# ALIM_MOSFET.net
KiCad netlist of a schematic drawn in Altium Designer
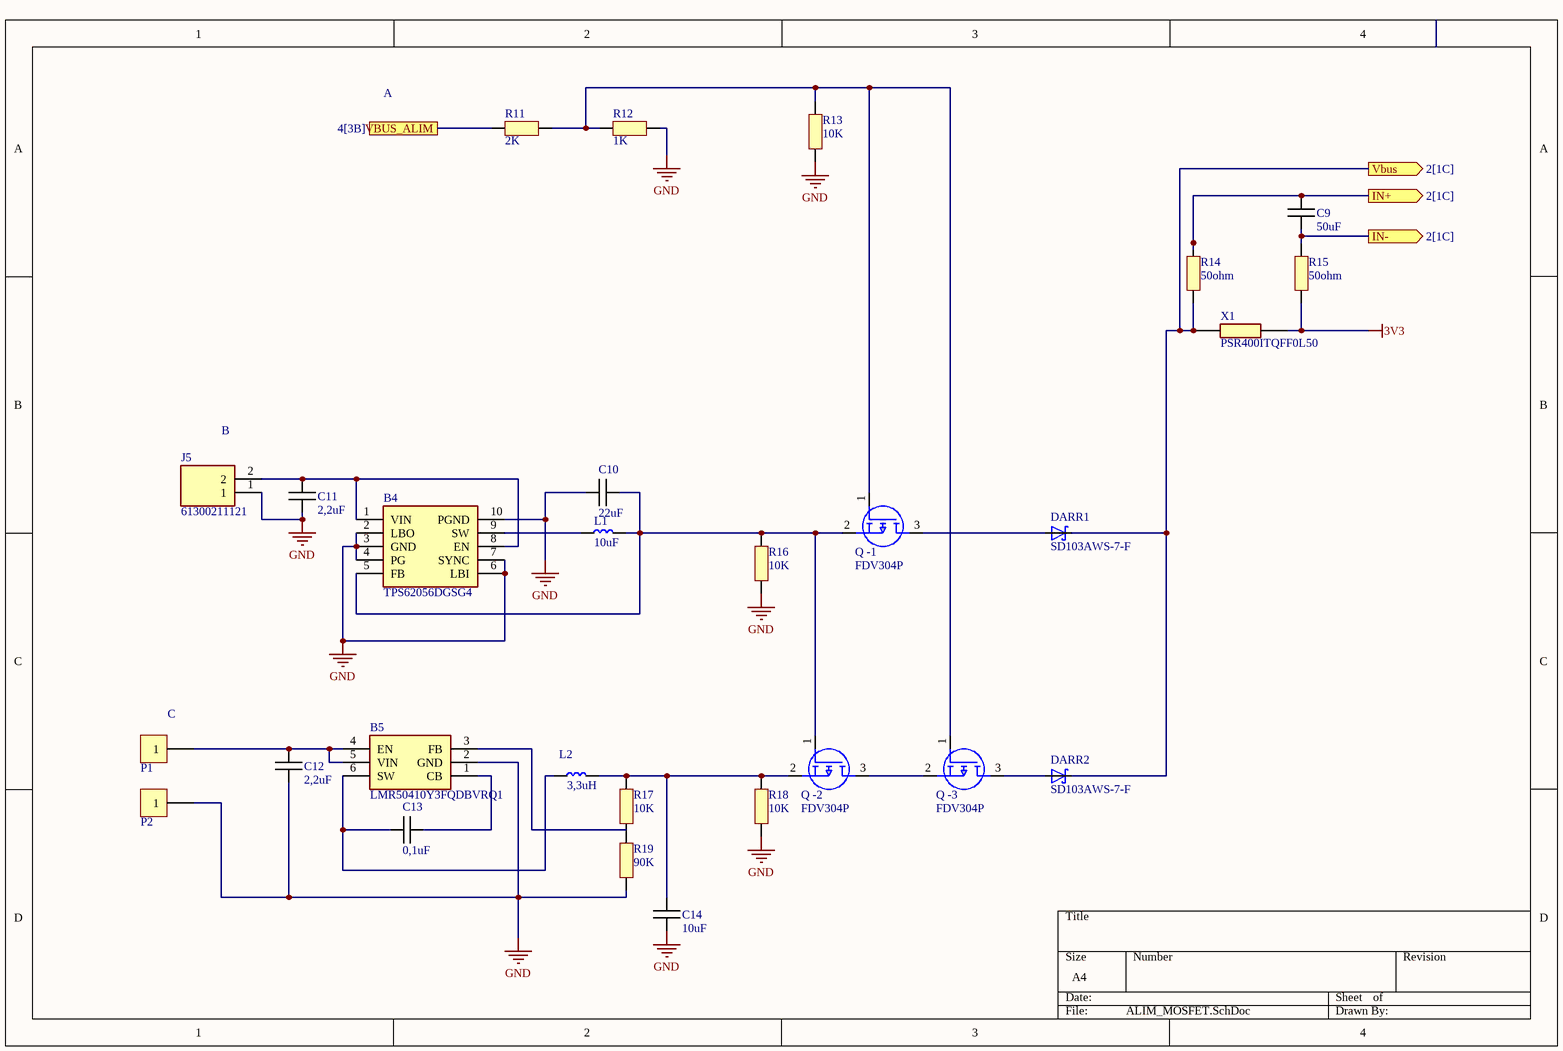
[diagram p0: ALIM_MOSFET.SchDoc]

(export (version "E")
  (design (tool "Eeschema 10.0.6"))
  (components
    (comp (ref "B4")
      (value "TPS62056DGSG4")
      (footprint "SOP50P490X110-10N")
      (fields (field (name "MOUSER PART NUMBER") "595-TPS62056DGSG4"))
      (libsource (lib "SCHLibrary") (part "TPS62056DGSG4"))
    )
    (comp (ref "B5")
      (value "LMR50410Y3FQDBVRQ1")
      (footprint "SOT95P280X145-6N")
      (fields (field (name "MOUSER PART NUMBER") "595-R50410Y3FQDBVRQ1"))
      (libsource (lib "SCHLibrary") (part "LMR50410Y3FQDBVRQ1"))
    )
    (comp (ref "C9")
      (value "50uF")
      (footprint "CAPC1005X06N")
      (libsource (lib "SCHLibrary") (part "Capacitor"))
    )
    (comp (ref "C10")
      (value "22uF")
      (footprint "CAPC1005X06N")
      (libsource (lib "SCHLibrary") (part "Capacitor"))
    )
    (comp (ref "C11")
      (value "2,2uF")
      (footprint "CAPC1005X06N")
      (libsource (lib "SCHLibrary") (part "Capacitor"))
    )
    (comp (ref "C12")
      (value "2,2uF")
      (footprint "CAPC1005X06N")
      (libsource (lib "SCHLibrary") (part "Capacitor"))
    )
    (comp (ref "C13")
      (value "0,1uF")
      (footprint "CAPC1005X06N")
      (libsource (lib "SCHLibrary") (part "Capacitor"))
    )
    (comp (ref "C14")
      (value "10uF")
      (footprint "CAPC1005X06N")
      (libsource (lib "SCHLibrary") (part "Capacitor"))
    )
    (comp (ref "DARR1")
      (value "SD103AWS-7-F")
      (footprint "SD103AWS-7-F")
      (description "Diode Array 3 Independent Schottky 40V 175mA Surface Mount 6-TSSOP, SC-88, SOT-363")
      (libsource (lib "SCHLibrary") (part "SD103AWS-7-F"))
    )
    (comp (ref "DARR2")
      (value "SD103AWS-7-F")
      (footprint "SD103AWS-7-F")
      (description "Diode Array 3 Independent Schottky 40V 175mA Surface Mount 6-TSSOP, SC-88, SOT-363")
      (libsource (lib "SCHLibrary") (part "SD103AWS-7-F"))
    )
    (comp (ref "J5")
      (value "61300211121")
      (footprint "61300211121")
      (description "WURTH ELEKTRONIK - 61300211121 - HEADER, 2.54MM, PIN, THT, VERTICAL, 2WAY")
      (libsource (lib "SCHLibrary") (part "61300211121"))
    )
    (comp (ref "L1") (value "10uF") (footprint "LQPC1005X06N") (libsource (lib "SCHLibrary") (part "Bobine")))
    (comp (ref "L2")
      (value "3,3uH")
      (footprint "LQPC1005X06N")
      (libsource (lib "SCHLibrary") (part "Bobine"))
    )
    (comp (ref "P1")
      (value "Plage CMS 10x5")
      (footprint "Plage CMS 10x5")
      (description "Plage de report CMS 10x5mm")
      (libsource (lib "SCHLibrary") (part "Plage CMS 10x5"))
    )
    (comp (ref "P2")
      (value "Plage CMS 10x5")
      (footprint "Plage CMS 10x5")
      (description "Plage de report CMS 10x5mm")
      (libsource (lib "SCHLibrary") (part "Plage CMS 10x5"))
    )
    (comp (ref "Q -1")
      (value "FDV304P")
      (footprint "SOT95P251X112-3N")
      (fields (field (name "MOUSER PART NUMBER") "512-FDV304P"))
      (libsource (lib "SCHLibrary") (part "FDV304P"))
    )
    (comp (ref "Q -2")
      (value "FDV304P")
      (footprint "SOT95P251X112-3N")
      (fields (field (name "MOUSER PART NUMBER") "512-FDV304P"))
      (libsource (lib "SCHLibrary") (part "FDV304P"))
    )
    (comp (ref "Q -3")
      (value "FDV304P")
      (footprint "SOT95P251X112-3N")
      (fields (field (name "MOUSER PART NUMBER") "512-FDV304P"))
      (libsource (lib "SCHLibrary") (part "FDV304P"))
    )
    (comp (ref "R11")
      (value "2K")
      (footprint "RESC1005X06N")
      (libsource (lib "SCHLibrary") (part "Resistor"))
    )
    (comp (ref "R12")
      (value "1K")
      (footprint "RESC1005X06N")
      (libsource (lib "SCHLibrary") (part "Resistor"))
    )
    (comp (ref "R13") (value "10K") (footprint "RESC1005X06N") (libsource (lib "") (part "Resistor_1")))
    (comp (ref "R14") (value "50ohm") (footprint "RESC1005X06N") (libsource (lib "") (part "Resistor_2")))
    (comp (ref "R15") (value "50ohm") (footprint "RESC1005X06N") (libsource (lib "") (part "Resistor_2")))
    (comp (ref "R16") (value "10K") (footprint "RESC1005X06N") (libsource (lib "") (part "Resistor_1")))
    (comp (ref "R17") (value "10K") (footprint "RESC1005X06N") (libsource (lib "") (part "Resistor_1")))
    (comp (ref "R18") (value "10K") (footprint "RESC1005X06N") (libsource (lib "") (part "Resistor_1")))
    (comp (ref "R19") (value "90K") (footprint "RESC1005X06N") (libsource (lib "") (part "Resistor_1")))
    (comp (ref "X1")
      (value "PSR400ITQFF0L50")
      (footprint "RESC10052X200N")
      (fields (field (name "MOUSER PART NUMBER") "755-PSR400ITQFF0L50"))
      (libsource (lib "SCHLibrary") (part "PSR400ITQFF0L50"))
    )
  )
  (nets
    (net (code "1") (name "/IN+") (class "Default")
      (node (ref "C9") (pin "1") (pinfunction "1_1") (pintype "passive"))
      (node (ref "R14") (pin "2") (pinfunction "2_2") (pintype "passive"))
    )
    (net (code "2") (name "/IN-") (class "Default")
      (node (ref "C9") (pin "2") (pinfunction "2_2") (pintype "passive"))
      (node (ref "R15") (pin "2") (pinfunction "2_2") (pintype "passive"))
    )
    (net (code "3") (name "/VBUS_ALIM") (class "Default")
      (node (ref "R11") (pin "1") (pinfunction "1_1") (pintype "passive"))
    )
    (net (code "4") (name "/Vbus") (class "Default")
      (node (ref "DARR1") (pin "1") (pinfunction "C_1") (pintype "passive"))
      (node (ref "DARR2") (pin "1") (pinfunction "C_1") (pintype "passive"))
      (node (ref "R14") (pin "1") (pinfunction "1_1") (pintype "passive"))
      (node (ref "X1") (pin "1") (pinfunction "1_1") (pintype "passive"))
    )
    (net (code "5") (name "3V3") (class "Default")
      (node (ref "R15") (pin "1") (pinfunction "1_1") (pintype "passive"))
      (node (ref "X1") (pin "2") (pinfunction "2_2") (pintype "passive"))
    )
    (net (code "6") (name "GND") (class "Default")
      (node (ref "B4") (pin "10") (pinfunction "PGND_10") (pintype "passive"))
      (node (ref "B4") (pin "2") (pinfunction "LBO_2") (pintype "passive"))
      (node (ref "B4") (pin "3") (pinfunction "GND_3") (pintype "passive"))
      (node (ref "B4") (pin "4") (pinfunction "PG_4") (pintype "passive"))
      (node (ref "B4") (pin "6") (pinfunction "LBI_6") (pintype "passive"))
      (node (ref "B4") (pin "7") (pinfunction "SYNC_7") (pintype "passive"))
      (node (ref "B5") (pin "2") (pinfunction "GND_2") (pintype "passive"))
      (node (ref "C10") (pin "2") (pinfunction "2_2") (pintype "passive"))
      (node (ref "C11") (pin "2") (pinfunction "2_2") (pintype "passive"))
      (node (ref "C12") (pin "2") (pinfunction "2_2") (pintype "passive"))
      (node (ref "C14") (pin "2") (pinfunction "2_2") (pintype "passive"))
      (node (ref "J5") (pin "1") (pinfunction "1_1") (pintype "passive"))
      (node (ref "P2") (pin "1") (pinfunction "1_1") (pintype "passive"))
      (node (ref "R12") (pin "2") (pinfunction "2_2") (pintype "passive"))
      (node (ref "R13") (pin "2") (pinfunction "2_2") (pintype "passive"))
      (node (ref "R16") (pin "2") (pinfunction "2_2") (pintype "passive"))
      (node (ref "R18") (pin "2") (pinfunction "2_2") (pintype "passive"))
      (node (ref "R19") (pin "2") (pinfunction "2_2") (pintype "passive"))
    )
    (net (code "7") (name "Net-(B4-EN)") (class "Default")
      (node (ref "B4") (pin "1") (pinfunction "VIN_1") (pintype "passive"))
      (node (ref "B4") (pin "8") (pinfunction "EN_8") (pintype "passive"))
      (node (ref "C11") (pin "1") (pinfunction "1_1") (pintype "passive"))
      (node (ref "J5") (pin "2") (pinfunction "2_2") (pintype "passive"))
    )
    (net (code "8") (name "Net-(B4-FB)") (class "Default")
      (node (ref "B4") (pin "5") (pinfunction "FB_5") (pintype "passive"))
      (node (ref "C10") (pin "1") (pinfunction "1_1") (pintype "passive"))
      (node (ref "L1") (pin "2") (pinfunction "2_2") (pintype "passive"))
      (node (ref "Q -1") (pin "2") (pinfunction "S_2") (pintype "passive"))
      (node (ref "Q -2") (pin "1") (pinfunction "G_1") (pintype "passive"))
      (node (ref "R16") (pin "1") (pinfunction "1_1") (pintype "passive"))
    )
    (net (code "9") (name "Net-(B4-SW)") (class "Default")
      (node (ref "B4") (pin "9") (pinfunction "SW_9") (pintype "passive"))
      (node (ref "L1") (pin "1") (pinfunction "1_1") (pintype "passive"))
    )
    (net (code "10") (name "Net-(B5-CB)") (class "Default")
      (node (ref "B5") (pin "1") (pinfunction "CB_1") (pintype "passive"))
      (node (ref "C13") (pin "1") (pinfunction "1_1") (pintype "passive"))
    )
    (net (code "11") (name "Net-(B5-EN)") (class "Default")
      (node (ref "B5") (pin "4") (pinfunction "EN_4") (pintype "passive"))
      (node (ref "B5") (pin "5") (pinfunction "VIN_5") (pintype "passive"))
      (node (ref "C12") (pin "1") (pinfunction "1_1") (pintype "passive"))
      (node (ref "P1") (pin "1") (pinfunction "1_1") (pintype "passive"))
    )
    (net (code "12") (name "Net-(B5-FB)") (class "Default")
      (node (ref "B5") (pin "3") (pinfunction "FB_3") (pintype "passive"))
      (node (ref "R19") (pin "1") (pinfunction "1_1") (pintype "passive"))
    )
    (net (code "13") (name "Net-(B5-SW)") (class "Default")
      (node (ref "B5") (pin "6") (pinfunction "SW_6") (pintype "passive"))
      (node (ref "C13") (pin "2") (pinfunction "2_2") (pintype "passive"))
      (node (ref "L2") (pin "1") (pinfunction "1_1") (pintype "passive"))
    )
    (net (code "14") (name "Net-(DARR1-A)") (class "Default")
      (node (ref "DARR1") (pin "2") (pinfunction "A_2") (pintype "passive"))
      (node (ref "Q -1") (pin "3") (pinfunction "D_3") (pintype "passive"))
    )
    (net (code "15") (name "Net-(DARR2-A)") (class "Default")
      (node (ref "DARR2") (pin "2") (pinfunction "A_2") (pintype "passive"))
      (node (ref "Q -3") (pin "3") (pinfunction "D_3") (pintype "passive"))
    )
    (net (code "16") (name "Net-(Q -1-G)") (class "Default")
      (node (ref "Q -1") (pin "1") (pinfunction "G_1") (pintype "passive"))
      (node (ref "Q -3") (pin "1") (pinfunction "G_1") (pintype "passive"))
      (node (ref "R11") (pin "2") (pinfunction "2_2") (pintype "passive"))
      (node (ref "R12") (pin "1") (pinfunction "1_1") (pintype "passive"))
      (node (ref "R13") (pin "1") (pinfunction "1_1") (pintype "passive"))
    )
    (net (code "17") (name "Net-(Q -2-D)") (class "Default")
      (node (ref "Q -2") (pin "3") (pinfunction "D_3") (pintype "passive"))
      (node (ref "Q -3") (pin "2") (pinfunction "S_2") (pintype "passive"))
    )
    (net (code "18") (name "Net-(Q -2-S)") (class "Default")
      (node (ref "C14") (pin "1") (pinfunction "1_1") (pintype "passive"))
      (node (ref "L2") (pin "2") (pinfunction "2_2") (pintype "passive"))
      (node (ref "Q -2") (pin "2") (pinfunction "S_2") (pintype "passive"))
      (node (ref "R17") (pin "1") (pinfunction "1_1") (pintype "passive"))
      (node (ref "R18") (pin "1") (pinfunction "1_1") (pintype "passive"))
    )
    (net (code "19") (name "unconnected-(R17-Pad2)") (class "Default")
      (node (ref "R17") (pin "2") (pinfunction "2_2") (pintype "passive"))
    )
  )
)
